# DRV8873.net
KiCad netlist of a schematic drawn in Altium Designer
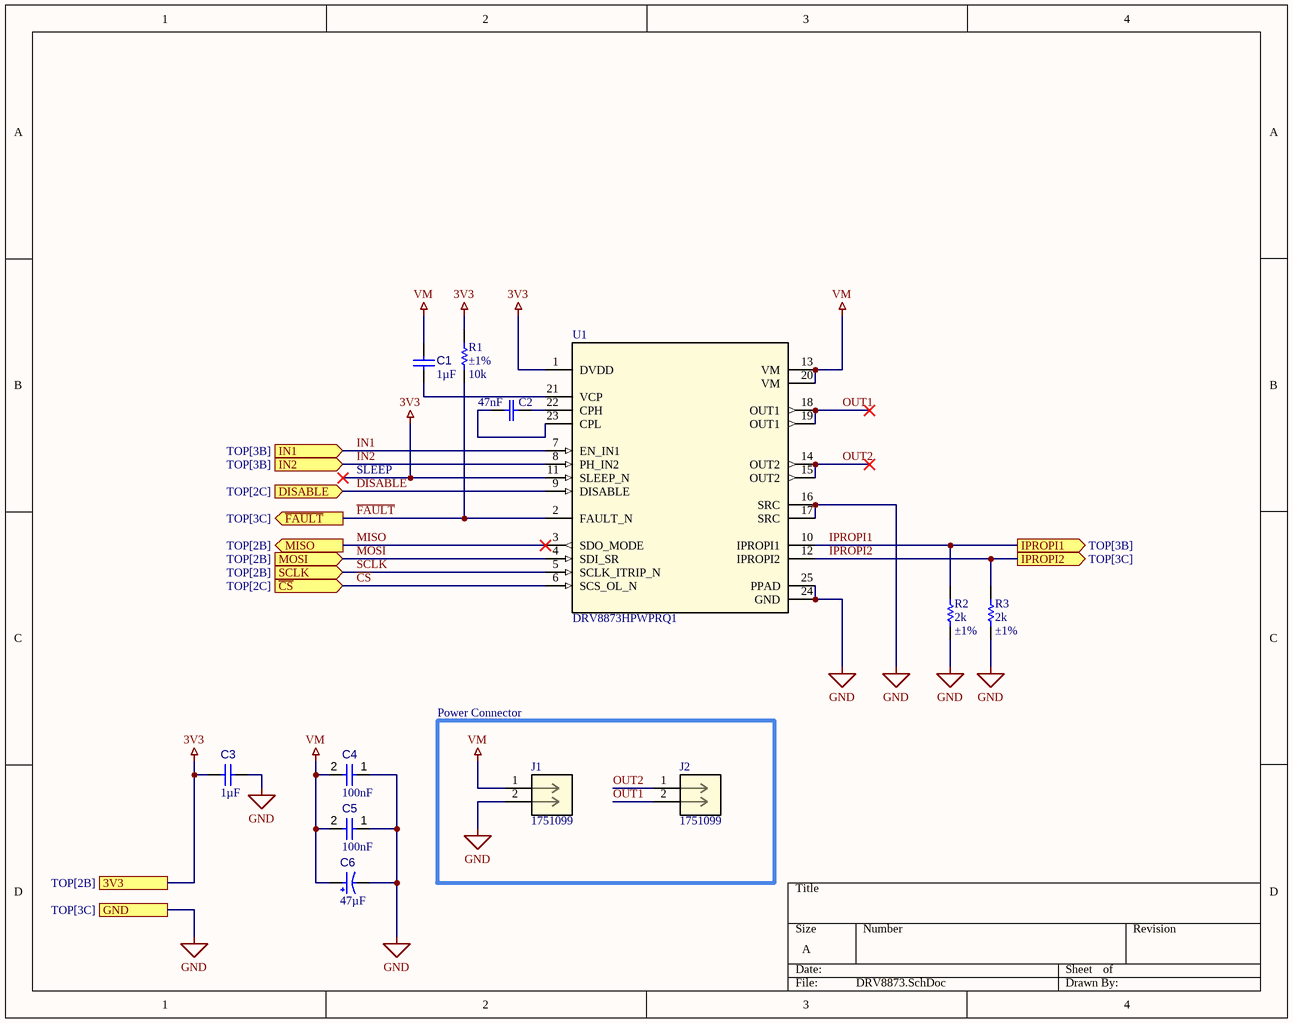
[diagram p0: DRV8873.SchDoc]

(export (version "E")
  (design (tool "Eeschema 10.0.6"))
  (components
    (comp (ref "C1")
      (value "1µF")
      (footprint "CAPC1608X94X35NL15T15")
      (description "Chip Capacitor, 1 uF, +/- 10%, 16 V, 0603 (1608 Metric)")
      (fields (field (name "TOLERANCE") "10%") (field (name "Comment") "Capacitor 1 uF +/- 10% 16 V 0603"))
      (libsource (lib "") (part "CAP-NP-2_1"))
    )
    (comp (ref "C2")
      (value "47nF")
      (footprint "CAPC220145_90N_KEM")
      (description "No Description Available")
      (libsource (lib "Altium Default Library") (part "C0805C473K5RACTU"))
    )
    (comp (ref "C3")
      (value "1µF")
      (footprint "CAPC1608X94X35NL15T15")
      (description "Chip Capacitor, 1 uF, +/- 10%, 16 V, 0603 (1608 Metric)")
      (fields (field (name "TOLERANCE") "10%") (field (name "Comment") "Capacitor 1 uF +/- 10% 16 V 0603"))
      (libsource (lib "") (part "CAP-NP-2_1"))
    )
    (comp (ref "C4")
      (value "100nF")
      (footprint "CAPC1608X90X40NL10T20")
      (description "Chip Capacitor, 100 nF, +/- 10%, 50 V, 0603 (1608 Metric)")
      (fields (field (name "TOLERANCE") "10%") (field (name "Comment") "Capacitor 100 nF +/-10% 50 V 0603"))
      (libsource (lib "Altium Default Library") (part "CAP-NP-2"))
    )
    (comp (ref "C5")
      (value "100nF")
      (footprint "CAPC1608X90X40NL10T20")
      (description "Chip Capacitor, 100 nF, +/- 10%, 50 V, 0603 (1608 Metric)")
      (fields (field (name "TOLERANCE") "10%") (field (name "Comment") "Capacitor 100 nF +/-10% 50 V 0603"))
      (libsource (lib "Altium Default Library") (part "CAP-NP-2"))
    )
    (comp (ref "C6")
      (value "47µF")
      (footprint "CAPPR55-250-1120X630X1220")
      (description "Aluminum Electrolytic Capacitor, 47 uF, +/-20%, 50 V, -40 to 85 degC, 2-Pin THD, RoHS, Bulk")
      (fields (field (name "TOLERANCE") "20%") (field (name "MANUFACTURER") "Panasonic"))
      (libsource (lib "Altium Default Library") (part "CAP-P-2"))
    )
    (comp (ref "J1")
      (value "1751099")
      (footprint "CONN_1751099_PXC")
      (description "No Description Available")
      (libsource (lib "Altium Default Library") (part "1751099"))
    )
    (comp (ref "J2")
      (value "1751099")
      (footprint "CONN_1751099_PXC")
      (description "No Description Available")
      (libsource (lib "Altium Default Library") (part "1751099"))
    )
    (comp (ref "R1")
      (value "~")
      (footprint "RESC0603L")
      (description "RES SMD 10K OHM 1% 1/10W 0603")
      (fields
        (field (name "TOLERANCE") "±1%")
        (field (name "MANUFACTURER") "Vishay Dale")
        (field (name "RESISTANCE") "10k")
        (field (name "MANUFACTURER PART NUMBER") "CRCW060310K0FKEA")
      )
      (libsource (lib "FUTEK Advanced Sensor Technology, Inc") (part "Resistor"))
    )
    (comp (ref "R2")
      (value "ERJ-P06F2001V")
      (footprint "RESC0805L")
      (description "RES SMD 2K OHM 1% 1/2W 0805")
      (fields
        (field (name "MANUFACTURER") "Panasonic Electronic Components")
        (field (name "RESISTANCE") "2k")
        (field (name "TOLERANCE") "±1%")
      )
      (libsource (lib "FUTEK Advanced Sensor Technology, Inc") (part "Resistor"))
    )
    (comp (ref "R3")
      (value "ERJ-P06F2001V")
      (footprint "RESC0805L")
      (description "RES SMD 2K OHM 1% 1/2W 0805")
      (fields
        (field (name "MANUFACTURER") "Panasonic Electronic Components")
        (field (name "RESISTANCE") "2k")
        (field (name "TOLERANCE") "±1%")
      )
      (libsource (lib "FUTEK Advanced Sensor Technology, Inc") (part "Resistor"))
    )
    (comp (ref "U1")
      (value "DRV8873HPWPRQ1")
      (footprint "PWP0024J_N")
      (description "No Description Available")
      (libsource (lib "Altium Default Library") (part "DRV8873HPWPRQ1"))
    )
  )
  (nets
    (net (code "1") (name "/DISABLE") (class "Default")
      (node (ref "U1") (pin "9") (pinfunction "DISABLE_9") (pintype "input"))
    )
    (net (code "2") (name "/IN1") (class "Default")
      (node (ref "U1") (pin "7") (pinfunction "EN_IN1_7") (pintype "input"))
    )
    (net (code "3") (name "/IN2") (class "Default")
      (node (ref "U1") (pin "8") (pinfunction "PH_IN2_8") (pintype "input"))
    )
    (net (code "4") (name "/IPROPI1") (class "Default")
      (node (ref "R2") (pin "2") (pinfunction "2_2") (pintype "passive"))
      (node (ref "U1") (pin "10") (pinfunction "IPROPI1_10") (pintype "passive"))
    )
    (net (code "5") (name "/IPROPI2") (class "Default")
      (node (ref "R3") (pin "2") (pinfunction "2_2") (pintype "passive"))
      (node (ref "U1") (pin "12") (pinfunction "IPROPI2_12") (pintype "passive"))
    )
    (net (code "6") (name "/MISO") (class "Default")
      (node (ref "U1") (pin "3") (pinfunction "SDO_MODE_3") (pintype "output+no_connect"))
    )
    (net (code "7") (name "/MOSI") (class "Default")
      (node (ref "U1") (pin "4") (pinfunction "SDI_SR_4") (pintype "input"))
    )
    (net (code "8") (name "/OUT1") (class "Default")
      (node (ref "J2") (pin "2") (pinfunction "2_2") (pintype "passive"))
      (node (ref "U1") (pin "18") (pinfunction "OUT1_18") (pintype "output"))
      (node (ref "U1") (pin "19") (pinfunction "OUT1_19") (pintype "output"))
    )
    (net (code "9") (name "/OUT2") (class "Default")
      (node (ref "J2") (pin "1") (pinfunction "1_1") (pintype "passive"))
      (node (ref "U1") (pin "14") (pinfunction "OUT2_14") (pintype "output"))
      (node (ref "U1") (pin "15") (pinfunction "OUT2_15") (pintype "output"))
    )
    (net (code "10") (name "/SCLK") (class "Default")
      (node (ref "U1") (pin "5") (pinfunction "SCLK_ITRIP_N_5") (pintype "input"))
    )
    (net (code "11") (name "/~{CS}") (class "Default")
      (node (ref "U1") (pin "6") (pinfunction "SCS_OL_N_6") (pintype "input"))
    )
    (net (code "12") (name "/~{FAULT}") (class "Default")
      (node (ref "R1") (pin "1") (pinfunction "1_1") (pintype "passive"))
      (node (ref "U1") (pin "2") (pinfunction "FAULT_N_2") (pintype "open_collector"))
    )
    (net (code "13") (name "3V3") (class "Default")
      (node (ref "C3") (pin "2") (pinfunction "2_2") (pintype "passive"))
      (node (ref "R1") (pin "2") (pinfunction "2_2") (pintype "passive"))
      (node (ref "U1") (pin "1") (pinfunction "DVDD_1") (pintype "power_in"))
      (node (ref "U1") (pin "11") (pinfunction "SLEEP_N_11") (pintype "input"))
    )
    (net (code "14") (name "GND") (class "Default")
      (node (ref "C3") (pin "1") (pinfunction "1_1") (pintype "passive"))
      (node (ref "C4") (pin "1") (pinfunction "1_1") (pintype "passive"))
      (node (ref "C5") (pin "1") (pinfunction "1_1") (pintype "passive"))
      (node (ref "C6") (pin "2") (pinfunction "2_2") (pintype "passive"))
      (node (ref "J1") (pin "2") (pinfunction "2_2") (pintype "passive"))
      (node (ref "R2") (pin "1") (pinfunction "1_1") (pintype "passive"))
      (node (ref "R3") (pin "1") (pinfunction "1_1") (pintype "passive"))
      (node (ref "U1") (pin "16") (pinfunction "SRC_16") (pintype "passive"))
      (node (ref "U1") (pin "17") (pinfunction "SRC_17") (pintype "passive"))
      (node (ref "U1") (pin "24") (pinfunction "GND_24") (pintype "power_in"))
      (node (ref "U1") (pin "25") (pinfunction "PPAD_25") (pintype "power_in"))
    )
    (net (code "15") (name "Net-(U1-CPH)") (class "Default")
      (node (ref "C2") (pin "2") (pinfunction "2_2") (pintype "passive"))
      (node (ref "U1") (pin "22") (pinfunction "CPH_22") (pintype "power_in"))
    )
    (net (code "16") (name "Net-(U1-CPL)") (class "Default")
      (node (ref "C2") (pin "1") (pinfunction "1_1") (pintype "passive"))
      (node (ref "U1") (pin "23") (pinfunction "CPL_23") (pintype "power_in"))
    )
    (net (code "17") (name "Net-(U1-VCP)") (class "Default")
      (node (ref "C1") (pin "1") (pinfunction "1_1") (pintype "passive"))
      (node (ref "U1") (pin "21") (pinfunction "VCP_21") (pintype "power_in"))
    )
    (net (code "18") (name "VM") (class "Default")
      (node (ref "C1") (pin "2") (pinfunction "2_2") (pintype "passive"))
      (node (ref "C4") (pin "2") (pinfunction "2_2") (pintype "passive"))
      (node (ref "C5") (pin "2") (pinfunction "2_2") (pintype "passive"))
      (node (ref "C6") (pin "1") (pinfunction "1_1") (pintype "passive"))
      (node (ref "J1") (pin "1") (pinfunction "1_1") (pintype "passive"))
      (node (ref "U1") (pin "13") (pinfunction "VM_13") (pintype "power_in"))
      (node (ref "U1") (pin "20") (pinfunction "VM_20") (pintype "power_in"))
    )
  )
)
